# Breakout_board_v3.net
KiCad netlist of a schematic drawn in Altium Designer
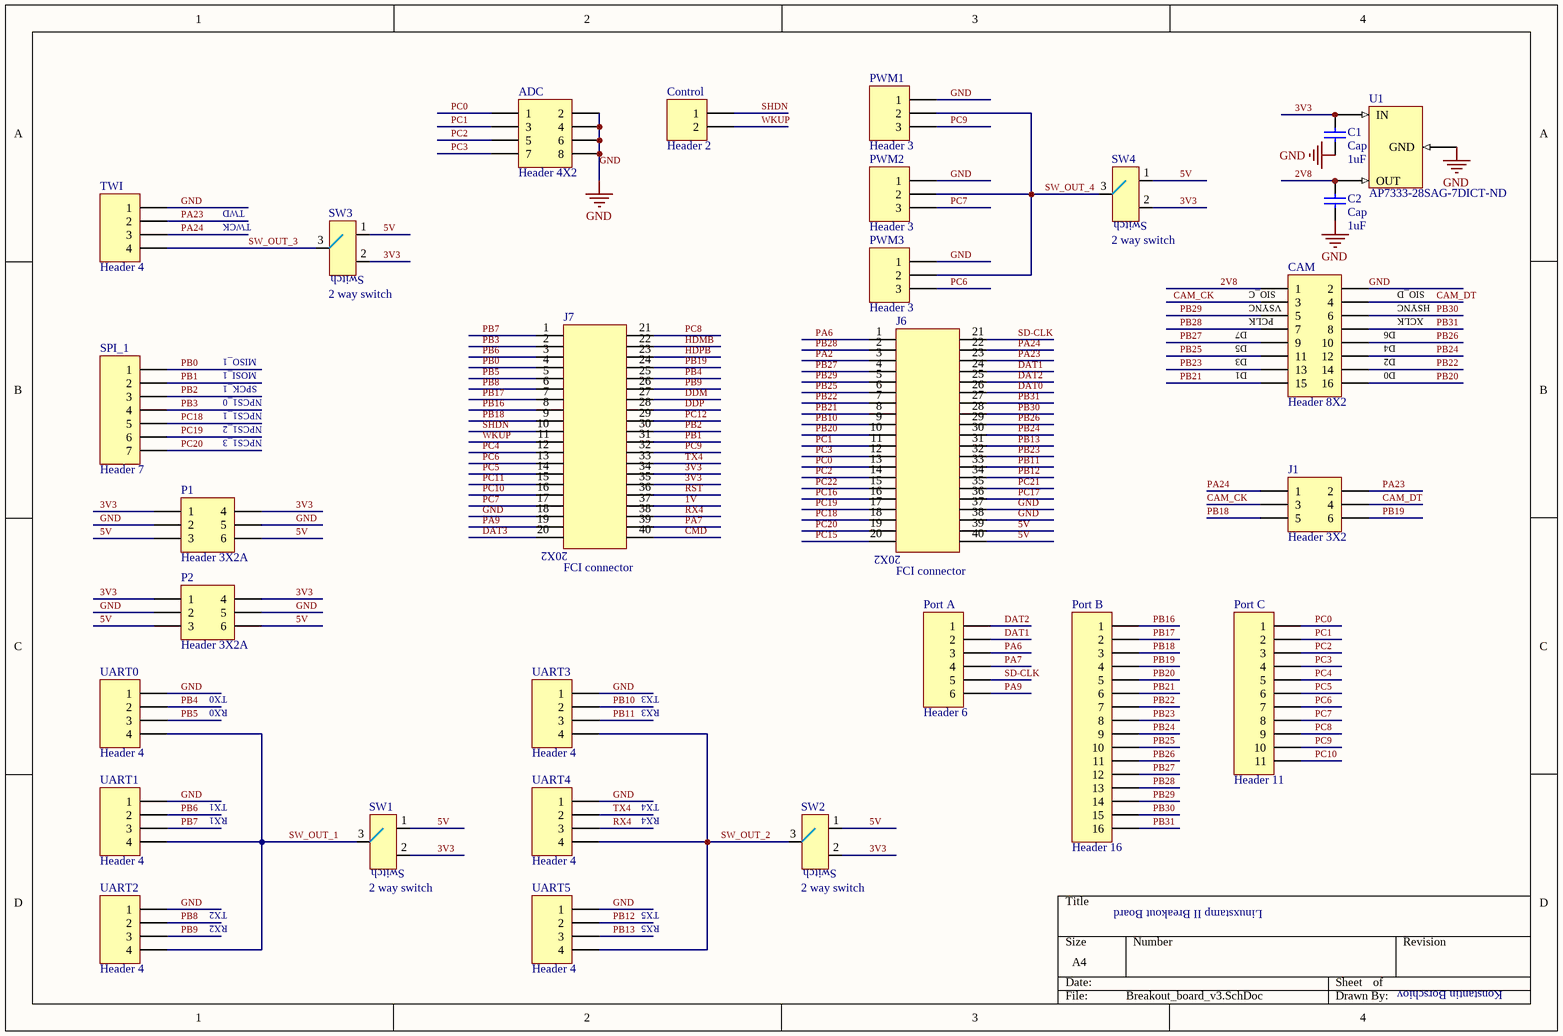
[diagram p0: Breakout_board_v3.SchDoc]

(export (version "E")
  (design (tool "Eeschema 10.0.6"))
  (components
    (comp (ref "ADC")
      (value "Header 4X2")
      (footprint "HDR2X4")
      (description "Header, 4-Pin, Dual row")
      (fields (field (name "PUBLISHER") "Altium Limited"))
      (libsource (lib "Miscellaneous Connectors") (part "Header 4X2"))
    )
    (comp (ref "C1")
      (value "Cap")
      (footprint "CAPR2.54-5.1x3.2")
      (description "Capacitor")
      (fields (field (name "ALTIUM_VALUE") "1uF") (field (name "PUBLISHER") "Altium Limited"))
      (libsource (lib "Miscellaneous Devices") (part "Cap"))
    )
    (comp (ref "C2")
      (value "Cap")
      (footprint "CAPR2.54-5.1x3.2")
      (description "Capacitor")
      (fields (field (name "ALTIUM_VALUE") "1uF") (field (name "PUBLISHER") "Altium Limited"))
      (libsource (lib "Miscellaneous Devices") (part "Cap"))
    )
    (comp (ref "CAM")
      (value "Header 8X2")
      (footprint "HDR2X8")
      (description "Header, 8-Pin, Dual row")
      (fields (field (name "PUBLISHER") "Altium Limited"))
      (libsource (lib "Miscellaneous Connectors") (part "Header 8X2"))
    )
    (comp (ref "Control")
      (value "Header 2")
      (footprint "HDR1X2")
      (description "Header, 2-Pin")
      (fields (field (name "PUBLISHER") "Altium Limited"))
      (libsource (lib "Miscellaneous Connectors") (part "Header 2"))
    )
    (comp (ref "J1")
      (value "Header 3X2")
      (footprint "HDR2X3")
      (description "Header, 3-Pin, Dual row")
      (fields (field (name "PUBLISHER") "Altium Limited"))
      (libsource (lib "Miscellaneous Connectors") (part "Header 3X2"))
    )
    (comp (ref "J6")
      (value "FCI connector")
      (footprint "FCI_61082_041402LF")
      (description "40 pin Dual in line connector")
      (libsource (lib "Linuxstamp_connector") (part "FCI connector"))
    )
    (comp (ref "J7")
      (value "FCI connector")
      (footprint "FCI_61082_041402LF")
      (description "40 pin Dual in line connector")
      (libsource (lib "Linuxstamp_connector") (part "FCI connector"))
    )
    (comp (ref "P1")
      (value "Header 3X2A")
      (footprint "HDR2X3_CEN")
      (description "Header, 3-Pin, Dual row")
      (fields (field (name "PUBLISHER") "Altium Limited"))
      (libsource (lib "Miscellaneous Connectors") (part "Header 3X2A"))
    )
    (comp (ref "P2")
      (value "Header 3X2A")
      (footprint "HDR2X3_CEN")
      (description "Header, 3-Pin, Dual row")
      (fields (field (name "PUBLISHER") "Altium Limited"))
      (libsource (lib "Miscellaneous Connectors") (part "Header 3X2A"))
    )
    (comp (ref "Port A")
      (value "Header 6")
      (footprint "HDR1X6")
      (description "Header, 6-Pin")
      (fields (field (name "PUBLISHER") "Altium Limited"))
      (libsource (lib "Miscellaneous Connectors") (part "Header 6"))
    )
    (comp (ref "Port B")
      (value "Header 16")
      (footprint "HDR1X16")
      (description "Header, 16-Pin")
      (fields (field (name "PUBLISHER") "Altium Limited"))
      (libsource (lib "Miscellaneous Connectors") (part "Header 16"))
    )
    (comp (ref "Port C")
      (value "Header 11")
      (footprint "HDR1X11")
      (description "Header, 11-Pin")
      (fields (field (name "PUBLISHER") "Altium Limited"))
      (libsource (lib "Miscellaneous Connectors") (part "Header 11"))
    )
    (comp (ref "PWM1")
      (value "Header 3")
      (footprint "HDR1X3")
      (description "Header, 3-Pin")
      (fields (field (name "PUBLISHER") "Altium Limited"))
      (libsource (lib "Miscellaneous Connectors") (part "Header 3"))
    )
    (comp (ref "PWM2")
      (value "Header 3")
      (footprint "HDR1X3")
      (description "Header, 3-Pin")
      (fields (field (name "PUBLISHER") "Altium Limited"))
      (libsource (lib "Miscellaneous Connectors") (part "Header 3"))
    )
    (comp (ref "PWM3")
      (value "Header 3")
      (footprint "HDR1X3")
      (description "Header, 3-Pin")
      (fields (field (name "PUBLISHER") "Altium Limited"))
      (libsource (lib "Miscellaneous Connectors") (part "Header 3"))
    )
    (comp (ref "SPI_1")
      (value "Header 7")
      (footprint "HDR1X7")
      (description "Header, 7-Pin")
      (fields (field (name "PUBLISHER") "Altium Limited"))
      (libsource (lib "Miscellaneous Connectors") (part "Header 7"))
    )
    (comp (ref "SW1")
      (value "2 way switch")
      (footprint "Tyco_SLS121PC04")
      (libsource (lib "Linuxstamp_connector") (part "Tyco_SLS121PC04"))
    )
    (comp (ref "SW2")
      (value "2 way switch")
      (footprint "Tyco_SLS121PC04")
      (libsource (lib "Linuxstamp_connector") (part "Tyco_SLS121PC04"))
    )
    (comp (ref "SW3")
      (value "2 way switch")
      (footprint "Tyco_SLS121PC04")
      (libsource (lib "Linuxstamp_connector") (part "Tyco_SLS121PC04"))
    )
    (comp (ref "SW4")
      (value "2 way switch")
      (footprint "Tyco_SLS121PC04")
      (libsource (lib "Linuxstamp_connector") (part "Tyco_SLS121PC04"))
    )
    (comp (ref "TWI")
      (value "Header 4")
      (footprint "HDR1X4")
      (description "Header, 4-Pin")
      (fields (field (name "PUBLISHER") "Altium Limited"))
      (libsource (lib "Miscellaneous Connectors") (part "Header 4"))
    )
    (comp (ref "U1")
      (value "Voltage Regulator - Linear, 2.8V output")
      (footprint "PCBComponent_1")
      (fields (field (name "SUPPLIER PART NUMBER 1") "AP7333-28SAG-7DICT-ND"))
      (libsource (lib "Diodes INC") (part "Voltage Regulator - Linear, 2.8V output"))
    )
    (comp (ref "UART0")
      (value "Header 4")
      (footprint "HDR1X4")
      (description "Header, 4-Pin")
      (fields (field (name "PUBLISHER") "Altium Limited"))
      (libsource (lib "Miscellaneous Connectors") (part "Header 4"))
    )
    (comp (ref "UART1")
      (value "Header 4")
      (footprint "HDR1X4")
      (description "Header, 4-Pin")
      (fields (field (name "PUBLISHER") "Altium Limited"))
      (libsource (lib "Miscellaneous Connectors") (part "Header 4"))
    )
    (comp (ref "UART2")
      (value "Header 4")
      (footprint "HDR1X4")
      (description "Header, 4-Pin")
      (fields (field (name "PUBLISHER") "Altium Limited"))
      (libsource (lib "Miscellaneous Connectors") (part "Header 4"))
    )
    (comp (ref "UART3")
      (value "Header 4")
      (footprint "HDR1X4")
      (description "Header, 4-Pin")
      (fields (field (name "PUBLISHER") "Altium Limited"))
      (libsource (lib "Miscellaneous Connectors") (part "Header 4"))
    )
    (comp (ref "UART4")
      (value "Header 4")
      (footprint "HDR1X4")
      (description "Header, 4-Pin")
      (fields (field (name "PUBLISHER") "Altium Limited"))
      (libsource (lib "Miscellaneous Connectors") (part "Header 4"))
    )
    (comp (ref "UART5")
      (value "Header 4")
      (footprint "HDR1X4")
      (description "Header, 4-Pin")
      (fields (field (name "PUBLISHER") "Altium Limited"))
      (libsource (lib "Miscellaneous Connectors") (part "Header 4"))
    )
  )
  (nets
    (net (code "1") (name "/1V") (class "Default")
      (node (ref "J7") (pin "37") (pinfunction "37_37") (pintype "passive"))
    )
    (net (code "2") (name "/2V8") (class "Default")
      (node (ref "C2") (pin "2") (pinfunction "2_2") (pintype "passive"))
      (node (ref "CAM") (pin "1") (pinfunction "1_1") (pintype "passive"))
      (node (ref "U1") (pin "1") (pinfunction "OUT_1") (pintype "input"))
    )
    (net (code "3") (name "/3V3") (class "Default")
      (node (ref "C1") (pin "2") (pinfunction "2_2") (pintype "passive"))
      (node (ref "J7") (pin "34") (pinfunction "34_34") (pintype "passive"))
      (node (ref "J7") (pin "35") (pinfunction "35_35") (pintype "passive"))
      (node (ref "P1") (pin "1") (pinfunction "1_1") (pintype "passive"))
      (node (ref "P1") (pin "4") (pinfunction "4_4") (pintype "passive"))
      (node (ref "P2") (pin "1") (pinfunction "1_1") (pintype "passive"))
      (node (ref "P2") (pin "4") (pinfunction "4_4") (pintype "passive"))
      (node (ref "SW1") (pin "2") (pinfunction "2_2") (pintype "passive"))
      (node (ref "SW2") (pin "2") (pinfunction "2_2") (pintype "passive"))
      (node (ref "SW3") (pin "2") (pinfunction "2_2") (pintype "passive"))
      (node (ref "SW4") (pin "2") (pinfunction "2_2") (pintype "passive"))
      (node (ref "U1") (pin "0") (pinfunction "IN_0") (pintype "input"))
    )
    (net (code "4") (name "/5V") (class "Default")
      (node (ref "J6") (pin "39") (pinfunction "39_39") (pintype "passive"))
      (node (ref "J6") (pin "40") (pinfunction "40_40") (pintype "passive"))
      (node (ref "P1") (pin "3") (pinfunction "3_3") (pintype "passive"))
      (node (ref "P1") (pin "6") (pinfunction "6_6") (pintype "passive"))
      (node (ref "P2") (pin "3") (pinfunction "3_3") (pintype "passive"))
      (node (ref "P2") (pin "6") (pinfunction "6_6") (pintype "passive"))
      (node (ref "SW1") (pin "1") (pinfunction "1_1") (pintype "passive"))
      (node (ref "SW2") (pin "1") (pinfunction "1_1") (pintype "passive"))
      (node (ref "SW3") (pin "1") (pinfunction "1_1") (pintype "passive"))
      (node (ref "SW4") (pin "1") (pinfunction "1_1") (pintype "passive"))
    )
    (net (code "5") (name "/CAM_CK") (class "Default")
      (node (ref "CAM") (pin "3") (pinfunction "3_3") (pintype "passive"))
      (node (ref "J1") (pin "3") (pinfunction "3_3") (pintype "passive"))
    )
    (net (code "6") (name "/CAM_DT") (class "Default")
      (node (ref "CAM") (pin "4") (pinfunction "4_4") (pintype "passive"))
      (node (ref "J1") (pin "4") (pinfunction "4_4") (pintype "passive"))
    )
    (net (code "7") (name "/CMD") (class "Default")
      (node (ref "J7") (pin "40") (pinfunction "40_40") (pintype "passive"))
    )
    (net (code "8") (name "/DAT0") (class "Default")
      (node (ref "J6") (pin "26") (pinfunction "26_26") (pintype "passive"))
    )
    (net (code "9") (name "/DAT1") (class "Default")
      (node (ref "J6") (pin "24") (pinfunction "24_24") (pintype "passive"))
      (node (ref "Port A") (pin "2") (pinfunction "2_2") (pintype "passive"))
    )
    (net (code "10") (name "/DAT2") (class "Default")
      (node (ref "J6") (pin "25") (pinfunction "25_25") (pintype "passive"))
      (node (ref "Port A") (pin "1") (pinfunction "1_1") (pintype "passive"))
    )
    (net (code "11") (name "/DAT3") (class "Default")
      (node (ref "J7") (pin "20") (pinfunction "20_20") (pintype "passive"))
    )
    (net (code "12") (name "/DDM") (class "Default")
      (node (ref "J7") (pin "27") (pinfunction "27_27") (pintype "passive"))
    )
    (net (code "13") (name "/DDP") (class "Default")
      (node (ref "J7") (pin "28") (pinfunction "28_28") (pintype "passive"))
    )
    (net (code "14") (name "/HDMB") (class "Default")
      (node (ref "J7") (pin "22") (pinfunction "22_22") (pintype "passive"))
    )
    (net (code "15") (name "/HDPB") (class "Default")
      (node (ref "J7") (pin "23") (pinfunction "23_23") (pintype "passive"))
    )
    (net (code "16") (name "/PA2") (class "Default")
      (node (ref "J6") (pin "3") (pinfunction "3_3") (pintype "passive"))
    )
    (net (code "17") (name "/PA6") (class "Default")
      (node (ref "J6") (pin "1") (pinfunction "1_1") (pintype "passive"))
      (node (ref "Port A") (pin "3") (pinfunction "3_3") (pintype "passive"))
    )
    (net (code "18") (name "/PA7") (class "Default")
      (node (ref "J7") (pin "39") (pinfunction "39_39") (pintype "passive"))
      (node (ref "Port A") (pin "4") (pinfunction "4_4") (pintype "passive"))
    )
    (net (code "19") (name "/PA9") (class "Default")
      (node (ref "J7") (pin "19") (pinfunction "19_19") (pintype "passive"))
      (node (ref "Port A") (pin "6") (pinfunction "6_6") (pintype "passive"))
    )
    (net (code "20") (name "/PA23") (class "Default")
      (node (ref "J1") (pin "2") (pinfunction "2_2") (pintype "passive"))
      (node (ref "J6") (pin "23") (pinfunction "23_23") (pintype "passive"))
      (node (ref "TWI") (pin "2") (pinfunction "2_2") (pintype "passive"))
    )
    (net (code "21") (name "/PA24") (class "Default")
      (node (ref "J1") (pin "1") (pinfunction "1_1") (pintype "passive"))
      (node (ref "J6") (pin "22") (pinfunction "22_22") (pintype "passive"))
      (node (ref "TWI") (pin "3") (pinfunction "3_3") (pintype "passive"))
    )
    (net (code "22") (name "/PB0") (class "Default")
      (node (ref "J7") (pin "4") (pinfunction "4_4") (pintype "passive"))
      (node (ref "SPI_1") (pin "1") (pinfunction "1_1") (pintype "passive"))
    )
    (net (code "23") (name "/PB1") (class "Default")
      (node (ref "J7") (pin "31") (pinfunction "31_31") (pintype "passive"))
      (node (ref "SPI_1") (pin "2") (pinfunction "2_2") (pintype "passive"))
    )
    (net (code "24") (name "/PB2") (class "Default")
      (node (ref "J7") (pin "30") (pinfunction "30_30") (pintype "passive"))
      (node (ref "SPI_1") (pin "3") (pinfunction "3_3") (pintype "passive"))
    )
    (net (code "25") (name "/PB3") (class "Default")
      (node (ref "J7") (pin "2") (pinfunction "2_2") (pintype "passive"))
      (node (ref "SPI_1") (pin "4") (pinfunction "4_4") (pintype "passive"))
    )
    (net (code "26") (name "/PB4") (class "Default")
      (node (ref "J7") (pin "25") (pinfunction "25_25") (pintype "passive"))
      (node (ref "UART0") (pin "2") (pinfunction "2_2") (pintype "passive"))
    )
    (net (code "27") (name "/PB5") (class "Default")
      (node (ref "J7") (pin "5") (pinfunction "5_5") (pintype "passive"))
      (node (ref "UART0") (pin "3") (pinfunction "3_3") (pintype "passive"))
    )
    (net (code "28") (name "/PB6") (class "Default")
      (node (ref "J7") (pin "3") (pinfunction "3_3") (pintype "passive"))
      (node (ref "UART1") (pin "2") (pinfunction "2_2") (pintype "passive"))
    )
    (net (code "29") (name "/PB7") (class "Default")
      (node (ref "J7") (pin "1") (pinfunction "1_1") (pintype "passive"))
      (node (ref "UART1") (pin "3") (pinfunction "3_3") (pintype "passive"))
    )
    (net (code "30") (name "/PB8") (class "Default")
      (node (ref "J7") (pin "6") (pinfunction "6_6") (pintype "passive"))
      (node (ref "UART2") (pin "2") (pinfunction "2_2") (pintype "passive"))
    )
    (net (code "31") (name "/PB9") (class "Default")
      (node (ref "J7") (pin "26") (pinfunction "26_26") (pintype "passive"))
      (node (ref "UART2") (pin "3") (pinfunction "3_3") (pintype "passive"))
    )
    (net (code "32") (name "/PB10") (class "Default")
      (node (ref "J6") (pin "9") (pinfunction "9_9") (pintype "passive"))
      (node (ref "UART3") (pin "2") (pinfunction "2_2") (pintype "passive"))
    )
    (net (code "33") (name "/PB11") (class "Default")
      (node (ref "J6") (pin "33") (pinfunction "33_33") (pintype "passive"))
      (node (ref "UART3") (pin "3") (pinfunction "3_3") (pintype "passive"))
    )
    (net (code "34") (name "/PB12") (class "Default")
      (node (ref "J6") (pin "34") (pinfunction "34_34") (pintype "passive"))
      (node (ref "UART5") (pin "2") (pinfunction "2_2") (pintype "passive"))
    )
    (net (code "35") (name "/PB13") (class "Default")
      (node (ref "J6") (pin "31") (pinfunction "31_31") (pintype "passive"))
      (node (ref "UART5") (pin "3") (pinfunction "3_3") (pintype "passive"))
    )
    (net (code "36") (name "/PB16") (class "Default")
      (node (ref "J7") (pin "8") (pinfunction "8_8") (pintype "passive"))
      (node (ref "Port B") (pin "1") (pinfunction "1_1") (pintype "passive"))
    )
    (net (code "37") (name "/PB17") (class "Default")
      (node (ref "J7") (pin "7") (pinfunction "7_7") (pintype "passive"))
      (node (ref "Port B") (pin "2") (pinfunction "2_2") (pintype "passive"))
    )
    (net (code "38") (name "/PB18") (class "Default")
      (node (ref "J1") (pin "5") (pinfunction "5_5") (pintype "passive"))
      (node (ref "J7") (pin "9") (pinfunction "9_9") (pintype "passive"))
      (node (ref "Port B") (pin "3") (pinfunction "3_3") (pintype "passive"))
    )
    (net (code "39") (name "/PB19") (class "Default")
      (node (ref "J1") (pin "6") (pinfunction "6_6") (pintype "passive"))
      (node (ref "J7") (pin "24") (pinfunction "24_24") (pintype "passive"))
      (node (ref "Port B") (pin "4") (pinfunction "4_4") (pintype "passive"))
    )
    (net (code "40") (name "/PB20") (class "Default")
      (node (ref "CAM") (pin "16") (pinfunction "16_16") (pintype "passive"))
      (node (ref "J6") (pin "10") (pinfunction "10_10") (pintype "passive"))
      (node (ref "Port B") (pin "5") (pinfunction "5_5") (pintype "passive"))
    )
    (net (code "41") (name "/PB21") (class "Default")
      (node (ref "CAM") (pin "15") (pinfunction "15_15") (pintype "passive"))
      (node (ref "J6") (pin "8") (pinfunction "8_8") (pintype "passive"))
      (node (ref "Port B") (pin "6") (pinfunction "6_6") (pintype "passive"))
    )
    (net (code "42") (name "/PB22") (class "Default")
      (node (ref "CAM") (pin "14") (pinfunction "14_14") (pintype "passive"))
      (node (ref "J6") (pin "7") (pinfunction "7_7") (pintype "passive"))
      (node (ref "Port B") (pin "7") (pinfunction "7_7") (pintype "passive"))
    )
    (net (code "43") (name "/PB23") (class "Default")
      (node (ref "CAM") (pin "13") (pinfunction "13_13") (pintype "passive"))
      (node (ref "J6") (pin "32") (pinfunction "32_32") (pintype "passive"))
      (node (ref "Port B") (pin "8") (pinfunction "8_8") (pintype "passive"))
    )
    (net (code "44") (name "/PB24") (class "Default")
      (node (ref "CAM") (pin "12") (pinfunction "12_12") (pintype "passive"))
      (node (ref "J6") (pin "30") (pinfunction "30_30") (pintype "passive"))
      (node (ref "Port B") (pin "9") (pinfunction "9_9") (pintype "passive"))
    )
    (net (code "45") (name "/PB25") (class "Default")
      (node (ref "CAM") (pin "11") (pinfunction "11_11") (pintype "passive"))
      (node (ref "J6") (pin "6") (pinfunction "6_6") (pintype "passive"))
      (node (ref "Port B") (pin "10") (pinfunction "10_10") (pintype "passive"))
    )
    (net (code "46") (name "/PB26") (class "Default")
      (node (ref "CAM") (pin "10") (pinfunction "10_10") (pintype "passive"))
      (node (ref "J6") (pin "29") (pinfunction "29_29") (pintype "passive"))
      (node (ref "Port B") (pin "11") (pinfunction "11_11") (pintype "passive"))
    )
    (net (code "47") (name "/PB27") (class "Default")
      (node (ref "CAM") (pin "9") (pinfunction "9_9") (pintype "passive"))
      (node (ref "J6") (pin "4") (pinfunction "4_4") (pintype "passive"))
      (node (ref "Port B") (pin "12") (pinfunction "12_12") (pintype "passive"))
    )
    (net (code "48") (name "/PB28") (class "Default")
      (node (ref "CAM") (pin "7") (pinfunction "7_7") (pintype "passive"))
      (node (ref "J6") (pin "2") (pinfunction "2_2") (pintype "passive"))
      (node (ref "Port B") (pin "13") (pinfunction "13_13") (pintype "passive"))
    )
    (net (code "49") (name "/PB29") (class "Default")
      (node (ref "CAM") (pin "5") (pinfunction "5_5") (pintype "passive"))
      (node (ref "J6") (pin "5") (pinfunction "5_5") (pintype "passive"))
      (node (ref "Port B") (pin "14") (pinfunction "14_14") (pintype "passive"))
    )
    (net (code "50") (name "/PB30") (class "Default")
      (node (ref "CAM") (pin "6") (pinfunction "6_6") (pintype "passive"))
      (node (ref "J6") (pin "28") (pinfunction "28_28") (pintype "passive"))
      (node (ref "Port B") (pin "15") (pinfunction "15_15") (pintype "passive"))
    )
    (net (code "51") (name "/PB31") (class "Default")
      (node (ref "CAM") (pin "8") (pinfunction "8_8") (pintype "passive"))
      (node (ref "J6") (pin "27") (pinfunction "27_27") (pintype "passive"))
      (node (ref "Port B") (pin "16") (pinfunction "16_16") (pintype "passive"))
    )
    (net (code "52") (name "/PC0") (class "Default")
      (node (ref "ADC") (pin "1") (pinfunction "1_1") (pintype "passive"))
      (node (ref "J6") (pin "13") (pinfunction "13_13") (pintype "passive"))
      (node (ref "Port C") (pin "1") (pinfunction "1_1") (pintype "passive"))
    )
    (net (code "53") (name "/PC1") (class "Default")
      (node (ref "ADC") (pin "3") (pinfunction "3_3") (pintype "passive"))
      (node (ref "J6") (pin "11") (pinfunction "11_11") (pintype "passive"))
      (node (ref "Port C") (pin "2") (pinfunction "2_2") (pintype "passive"))
    )
    (net (code "54") (name "/PC2") (class "Default")
      (node (ref "ADC") (pin "5") (pinfunction "5_5") (pintype "passive"))
      (node (ref "J6") (pin "14") (pinfunction "14_14") (pintype "passive"))
      (node (ref "Port C") (pin "3") (pinfunction "3_3") (pintype "passive"))
    )
    (net (code "55") (name "/PC3") (class "Default")
      (node (ref "ADC") (pin "7") (pinfunction "7_7") (pintype "passive"))
      (node (ref "J6") (pin "12") (pinfunction "12_12") (pintype "passive"))
      (node (ref "Port C") (pin "4") (pinfunction "4_4") (pintype "passive"))
    )
    (net (code "56") (name "/PC4") (class "Default")
      (node (ref "J7") (pin "12") (pinfunction "12_12") (pintype "passive"))
      (node (ref "Port C") (pin "5") (pinfunction "5_5") (pintype "passive"))
    )
    (net (code "57") (name "/PC5") (class "Default")
      (node (ref "J7") (pin "14") (pinfunction "14_14") (pintype "passive"))
      (node (ref "Port C") (pin "6") (pinfunction "6_6") (pintype "passive"))
    )
    (net (code "58") (name "/PC6") (class "Default")
      (node (ref "J7") (pin "13") (pinfunction "13_13") (pintype "passive"))
      (node (ref "PWM3") (pin "3") (pinfunction "3_3") (pintype "passive"))
      (node (ref "Port C") (pin "7") (pinfunction "7_7") (pintype "passive"))
    )
    (net (code "59") (name "/PC7") (class "Default")
      (node (ref "J7") (pin "17") (pinfunction "17_17") (pintype "passive"))
      (node (ref "PWM2") (pin "3") (pinfunction "3_3") (pintype "passive"))
      (node (ref "Port C") (pin "8") (pinfunction "8_8") (pintype "passive"))
    )
    (net (code "60") (name "/PC8") (class "Default")
      (node (ref "J7") (pin "21") (pinfunction "21_21") (pintype "passive"))
      (node (ref "Port C") (pin "9") (pinfunction "9_9") (pintype "passive"))
    )
    (net (code "61") (name "/PC9") (class "Default")
      (node (ref "J7") (pin "32") (pinfunction "32_32") (pintype "passive"))
      (node (ref "PWM1") (pin "3") (pinfunction "3_3") (pintype "passive"))
      (node (ref "Port C") (pin "10") (pinfunction "10_10") (pintype "passive"))
    )
    (net (code "62") (name "/PC10") (class "Default")
      (node (ref "J7") (pin "16") (pinfunction "16_16") (pintype "passive"))
      (node (ref "Port C") (pin "11") (pinfunction "11_11") (pintype "passive"))
    )
    (net (code "63") (name "/PC11") (class "Default")
      (node (ref "J7") (pin "15") (pinfunction "15_15") (pintype "passive"))
    )
    (net (code "64") (name "/PC12") (class "Default")
      (node (ref "J7") (pin "29") (pinfunction "29_29") (pintype "passive"))
    )
    (net (code "65") (name "/PC15") (class "Default")
      (node (ref "J6") (pin "20") (pinfunction "20_20") (pintype "passive"))
    )
    (net (code "66") (name "/PC16") (class "Default")
      (node (ref "J6") (pin "16") (pinfunction "16_16") (pintype "passive"))
    )
    (net (code "67") (name "/PC17") (class "Default")
      (node (ref "J6") (pin "36") (pinfunction "36_36") (pintype "passive"))
    )
    (net (code "68") (name "/PC18") (class "Default")
      (node (ref "J6") (pin "18") (pinfunction "18_18") (pintype "passive"))
      (node (ref "SPI_1") (pin "5") (pinfunction "5_5") (pintype "passive"))
    )
    (net (code "69") (name "/PC19") (class "Default")
      (node (ref "J6") (pin "17") (pinfunction "17_17") (pintype "passive"))
      (node (ref "SPI_1") (pin "6") (pinfunction "6_6") (pintype "passive"))
    )
    (net (code "70") (name "/PC20") (class "Default")
      (node (ref "J6") (pin "19") (pinfunction "19_19") (pintype "passive"))
      (node (ref "SPI_1") (pin "7") (pinfunction "7_7") (pintype "passive"))
    )
    (net (code "71") (name "/PC21") (class "Default")
      (node (ref "J6") (pin "35") (pinfunction "35_35") (pintype "passive"))
    )
    (net (code "72") (name "/PC22") (class "Default")
      (node (ref "J6") (pin "15") (pinfunction "15_15") (pintype "passive"))
    )
    (net (code "73") (name "/RST") (class "Default")
      (node (ref "J7") (pin "36") (pinfunction "36_36") (pintype "passive"))
    )
    (net (code "74") (name "/RX4") (class "Default")
      (node (ref "J7") (pin "38") (pinfunction "38_38") (pintype "passive"))
      (node (ref "UART4") (pin "3") (pinfunction "3_3") (pintype "passive"))
    )
    (net (code "75") (name "/SD-CLK") (class "Default")
      (node (ref "J6") (pin "21") (pinfunction "21_21") (pintype "passive"))
      (node (ref "Port A") (pin "5") (pinfunction "5_5") (pintype "passive"))
    )
    (net (code "76") (name "/SHDN") (class "Default")
      (node (ref "Control") (pin "1") (pinfunction "1_1") (pintype "passive"))
      (node (ref "J7") (pin "10") (pinfunction "10_10") (pintype "passive"))
    )
    (net (code "77") (name "/SW_OUT_1") (class "Default")
      (node (ref "SW1") (pin "3") (pinfunction "3_3") (pintype "passive"))
      (node (ref "UART0") (pin "4") (pinfunction "4_4") (pintype "passive"))
      (node (ref "UART1") (pin "4") (pinfunction "4_4") (pintype "passive"))
      (node (ref "UART2") (pin "4") (pinfunction "4_4") (pintype "passive"))
    )
    (net (code "78") (name "/SW_OUT_2") (class "Default")
      (node (ref "SW2") (pin "3") (pinfunction "3_3") (pintype "passive"))
      (node (ref "UART3") (pin "4") (pinfunction "4_4") (pintype "passive"))
      (node (ref "UART4") (pin "4") (pinfunction "4_4") (pintype "passive"))
      (node (ref "UART5") (pin "4") (pinfunction "4_4") (pintype "passive"))
    )
    (net (code "79") (name "/SW_OUT_3") (class "Default")
      (node (ref "SW3") (pin "3") (pinfunction "3_3") (pintype "passive"))
      (node (ref "TWI") (pin "4") (pinfunction "4_4") (pintype "passive"))
    )
    (net (code "80") (name "/SW_OUT_4") (class "Default")
      (node (ref "PWM1") (pin "2") (pinfunction "2_2") (pintype "passive"))
      (node (ref "PWM2") (pin "2") (pinfunction "2_2") (pintype "passive"))
      (node (ref "PWM3") (pin "2") (pinfunction "2_2") (pintype "passive"))
      (node (ref "SW4") (pin "3") (pinfunction "3_3") (pintype "passive"))
    )
    (net (code "81") (name "/TX4") (class "Default")
      (node (ref "J7") (pin "33") (pinfunction "33_33") (pintype "passive"))
      (node (ref "UART4") (pin "2") (pinfunction "2_2") (pintype "passive"))
    )
    (net (code "82") (name "/WKUP") (class "Default")
      (node (ref "Control") (pin "2") (pinfunction "2_2") (pintype "passive"))
      (node (ref "J7") (pin "11") (pinfunction "11_11") (pintype "passive"))
    )
    (net (code "83") (name "GND") (class "Default")
      (node (ref "ADC") (pin "2") (pinfunction "2_2") (pintype "passive"))
      (node (ref "ADC") (pin "4") (pinfunction "4_4") (pintype "passive"))
      (node (ref "ADC") (pin "6") (pinfunction "6_6") (pintype "passive"))
      (node (ref "ADC") (pin "8") (pinfunction "8_8") (pintype "passive"))
      (node (ref "C1") (pin "1") (pinfunction "1_1") (pintype "passive"))
      (node (ref "C2") (pin "1") (pinfunction "1_1") (pintype "passive"))
      (node (ref "CAM") (pin "2") (pinfunction "2_2") (pintype "passive"))
      (node (ref "J6") (pin "37") (pinfunction "37_37") (pintype "passive"))
      (node (ref "J6") (pin "38") (pinfunction "38_38") (pintype "passive"))
      (node (ref "J7") (pin "18") (pinfunction "18_18") (pintype "passive"))
      (node (ref "P1") (pin "2") (pinfunction "2_2") (pintype "passive"))
      (node (ref "P1") (pin "5") (pinfunction "5_5") (pintype "passive"))
      (node (ref "P2") (pin "2") (pinfunction "2_2") (pintype "passive"))
      (node (ref "P2") (pin "5") (pinfunction "5_5") (pintype "passive"))
      (node (ref "PWM1") (pin "1") (pinfunction "1_1") (pintype "passive"))
      (node (ref "PWM2") (pin "1") (pinfunction "1_1") (pintype "passive"))
      (node (ref "PWM3") (pin "1") (pinfunction "1_1") (pintype "passive"))
      (node (ref "TWI") (pin "1") (pinfunction "1_1") (pintype "passive"))
      (node (ref "U1") (pin "2") (pinfunction "GND_2") (pintype "input"))
      (node (ref "UART0") (pin "1") (pinfunction "1_1") (pintype "passive"))
      (node (ref "UART1") (pin "1") (pinfunction "1_1") (pintype "passive"))
      (node (ref "UART2") (pin "1") (pinfunction "1_1") (pintype "passive"))
      (node (ref "UART3") (pin "1") (pinfunction "1_1") (pintype "passive"))
      (node (ref "UART4") (pin "1") (pinfunction "1_1") (pintype "passive"))
      (node (ref "UART5") (pin "1") (pinfunction "1_1") (pintype "passive"))
    )
  )
)
